# PCB2.net
KiCad netlist of a schematic drawn in Altium Designer
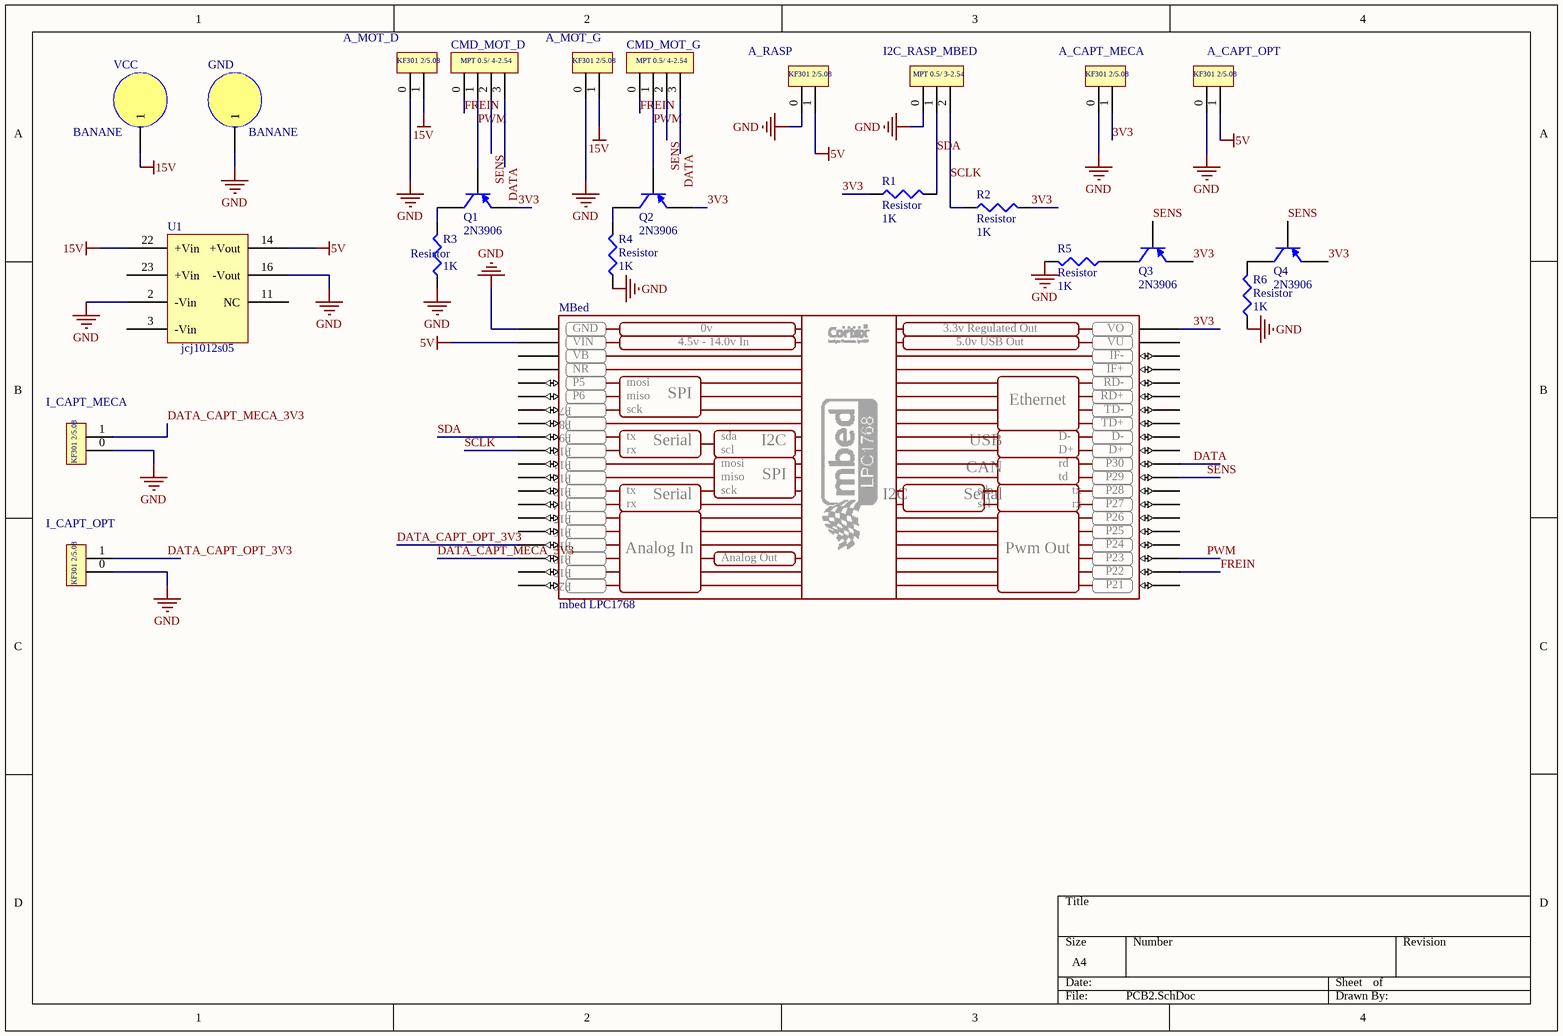
[diagram p0: PCB2.SchDoc]

(export (version "E")
  (design (tool "Eeschema 10.0.6"))
  (components
    (comp (ref "A_CAPT_MECA")
      (value "Screw Terminal 2/5.08")
      (footprint "KF301_2/5.08")
      (description "KF301 2 contacts / 5.08mm")
      (libsource (lib "Library_Polytech_Connector") (part "Screw Terminal 2/5.08"))
    )
    (comp (ref "A_CAPT_OPT")
      (value "Screw Terminal 2/5.08")
      (footprint "KF301_2/5.08")
      (description "KF301 2 contacts / 5.08mm")
      (libsource (lib "Library_Polytech_Connector") (part "Screw Terminal 2/5.08"))
    )
    (comp (ref "A_MOT_D")
      (value "Screw Terminal 2/5.08")
      (footprint "KF301_2/5.08")
      (description "KF301 2 contacts / 5.08mm")
      (libsource (lib "Library_Polytech_Connector") (part "Screw Terminal 2/5.08"))
    )
    (comp (ref "A_MOT_G")
      (value "Screw Terminal 2/5.08")
      (footprint "KF301_2/5.08")
      (description "KF301 2 contacts / 5.08mm")
      (libsource (lib "Library_Polytech_Connector") (part "Screw Terminal 2/5.08"))
    )
    (comp (ref "A_RASP")
      (value "Screw Terminal 2/5.08")
      (footprint "KF301_2/5.08")
      (description "KF301 2 contacts / 5.08mm")
      (libsource (lib "Library_Polytech_Connector") (part "Screw Terminal 2/5.08"))
    )
    (comp (ref "CMD_MOT_D")
      (value "Screw Terminal 4/2.54")
      (footprint "MPT_0.5-4-2.54")
      (description "MPT 0.5/ 4 contacts / 2.54mm")
      (libsource (lib "Library_Polytech_Connector") (part "Screw Terminal 4/2.54"))
    )
    (comp (ref "CMD_MOT_G")
      (value "Screw Terminal 4/2.54")
      (footprint "MPT_0.5-4-2.54")
      (description "MPT 0.5/ 4 contacts / 2.54mm")
      (libsource (lib "Library_Polytech_Connector") (part "Screw Terminal 4/2.54"))
    )
    (comp (ref "GND")
      (value "BANANE")
      (footprint "connecteur_banane_v0.1")
      (description "socket 4 mm with nut")
      (libsource (lib "Library_Polytech_Connector") (part "Socket 4 mm"))
    )
    (comp (ref "I2C_RASP_MBED")
      (value "Screw Terminal 3/2.54")
      (footprint "MPT_0.5-3-2.54")
      (description "MPT 0.5/ 3 contacts / 2.54mm")
      (libsource (lib "Library_Polytech_Connector") (part "Screw Terminal 3/2.54"))
    )
    (comp (ref "I_CAPT_MECA")
      (value "Screw Terminal 2/5.08")
      (footprint "KF301_2/5.08")
      (description "KF301 2 contacts / 5.08mm")
      (libsource (lib "") (part "Screw Terminal 2/5.08_1"))
    )
    (comp (ref "I_CAPT_OPT")
      (value "Screw Terminal 2/5.08")
      (footprint "KF301_2/5.08")
      (description "KF301 2 contacts / 5.08mm")
      (libsource (lib "") (part "Screw Terminal 2/5.08_1"))
    )
    (comp (ref "MBed")
      (value "mbed LPC1768")
      (footprint "DIP40-LARGE")
      (description "Prototyping Board")
      (libsource (lib "Library_Polytech_Actif") (part "mbed LPC1768"))
    )
    (comp (ref "Q1")
      (value "2N3906")
      (footprint "TO-92A")
      (description "PNP General Purpose Amplifier")
      (fields (field (name "PUBLISHER") "Altium Limited"))
      (libsource (lib "Miscellaneous Devices") (part "2N3906"))
    )
    (comp (ref "Q2")
      (value "2N3906")
      (footprint "TO-92A")
      (description "PNP General Purpose Amplifier")
      (fields (field (name "PUBLISHER") "Altium Limited"))
      (libsource (lib "Miscellaneous Devices") (part "2N3906"))
    )
    (comp (ref "Q3")
      (value "2N3906")
      (footprint "TO-92A")
      (description "PNP General Purpose Amplifier")
      (fields (field (name "PUBLISHER") "Altium Limited"))
      (libsource (lib "Miscellaneous Devices") (part "2N3906"))
    )
    (comp (ref "Q4")
      (value "2N3906")
      (footprint "TO-92A")
      (description "PNP General Purpose Amplifier")
      (fields (field (name "PUBLISHER") "Altium Limited"))
      (libsource (lib "Miscellaneous Devices") (part "2N3906"))
    )
    (comp (ref "R1")
      (value "Resistor")
      (footprint "AXIAL-0.6")
      (fields (field (name "ALTIUM_VALUE") "1K") (field (name "PUBLISHER") "Altium Limited"))
      (libsource (lib "Library_Polytech_Passif") (part "Resistor"))
    )
    (comp (ref "R2")
      (value "Resistor")
      (footprint "AXIAL-0.6")
      (fields (field (name "ALTIUM_VALUE") "1K") (field (name "PUBLISHER") "Altium Limited"))
      (libsource (lib "Library_Polytech_Passif") (part "Resistor"))
    )
    (comp (ref "R3")
      (value "Resistor")
      (footprint "AXIAL-0.6")
      (fields (field (name "ALTIUM_VALUE") "1K") (field (name "PUBLISHER") "Altium Limited"))
      (libsource (lib "Library_Polytech_Passif") (part "Resistor"))
    )
    (comp (ref "R4")
      (value "Resistor")
      (footprint "AXIAL-0.6")
      (fields (field (name "ALTIUM_VALUE") "1K") (field (name "PUBLISHER") "Altium Limited"))
      (libsource (lib "Library_Polytech_Passif") (part "Resistor"))
    )
    (comp (ref "R5")
      (value "Resistor")
      (footprint "AXIAL-0.6")
      (fields (field (name "ALTIUM_VALUE") "1K") (field (name "PUBLISHER") "Altium Limited"))
      (libsource (lib "Library_Polytech_Passif") (part "Resistor"))
    )
    (comp (ref "R6")
      (value "Resistor")
      (footprint "AXIAL-0.6")
      (fields (field (name "ALTIUM_VALUE") "1K") (field (name "PUBLISHER") "Altium Limited"))
      (libsource (lib "Library_Polytech_Passif") (part "Resistor"))
    )
    (comp (ref "U1")
      (value "jcj1012s05")
      (footprint "jcj1012s05")
      (libsource (lib "traveling") (part "jcj1012s05"))
    )
    (comp (ref "VCC")
      (value "BANANE")
      (footprint "connecteur_banane_v0.1")
      (description "socket 4 mm with nut")
      (libsource (lib "Library_Polytech_Connector") (part "Socket 4 mm"))
    )
  )
  (nets
    (net (code "1") (name "/3V3") (class "Default")
      (node (ref "A_CAPT_MECA") (pin "1") (pinfunction "1_1") (pintype "passive"))
      (node (ref "MBed") (pin "40") (pinfunction "VO_40") (pintype "power_in"))
      (node (ref "Q1") (pin "1") (pinfunction "E_1") (pintype "passive"))
      (node (ref "Q2") (pin "1") (pinfunction "E_1") (pintype "passive"))
      (node (ref "Q3") (pin "1") (pinfunction "E_1") (pintype "passive"))
      (node (ref "Q4") (pin "1") (pinfunction "E_1") (pintype "passive"))
      (node (ref "R1") (pin "1") (pinfunction "1_1") (pintype "passive"))
      (node (ref "R2") (pin "2") (pinfunction "2_2") (pintype "passive"))
    )
    (net (code "2") (name "/DATA") (class "Default")
      (node (ref "CMD_MOT_D") (pin "3") (pinfunction "3_3") (pintype "passive"))
      (node (ref "CMD_MOT_G") (pin "3") (pinfunction "3_3") (pintype "passive"))
      (node (ref "MBed") (pin "30") (pinfunction "P30_30") (pintype "bidirectional"))
    )
    (net (code "3") (name "/DATA_CAPT_MECA_3V3") (class "Default")
      (node (ref "I_CAPT_MECA") (pin "1") (pinfunction "1_1") (pintype "passive"))
      (node (ref "MBed") (pin "18") (pinfunction "P18_18") (pintype "bidirectional"))
    )
    (net (code "4") (name "/DATA_CAPT_OPT_3V3") (class "Default")
      (node (ref "I_CAPT_OPT") (pin "1") (pinfunction "1_1") (pintype "passive"))
      (node (ref "MBed") (pin "17") (pinfunction "P17_17") (pintype "bidirectional"))
    )
    (net (code "5") (name "/FREIN") (class "Default")
      (node (ref "CMD_MOT_D") (pin "0") (pinfunction "0_0") (pintype "passive"))
      (node (ref "CMD_MOT_G") (pin "0") (pinfunction "0_0") (pintype "passive"))
      (node (ref "MBed") (pin "22") (pinfunction "P22_22") (pintype "bidirectional"))
    )
    (net (code "6") (name "/PWM") (class "Default")
      (node (ref "CMD_MOT_D") (pin "1") (pinfunction "1_1") (pintype "passive"))
      (node (ref "CMD_MOT_G") (pin "1") (pinfunction "1_1") (pintype "passive"))
      (node (ref "MBed") (pin "23") (pinfunction "P23_23") (pintype "bidirectional"))
      (node (ref "Q1") (pin "2") (pinfunction "B_2") (pintype "passive"))
      (node (ref "Q2") (pin "2") (pinfunction "B_2") (pintype "passive"))
    )
    (net (code "7") (name "/SCLK") (class "Default")
      (node (ref "I2C_RASP_MBED") (pin "2") (pinfunction "2_2") (pintype "passive"))
      (node (ref "MBed") (pin "10") (pinfunction "P10_10") (pintype "bidirectional"))
      (node (ref "R2") (pin "1") (pinfunction "1_1") (pintype "passive"))
    )
    (net (code "8") (name "/SDA") (class "Default")
      (node (ref "I2C_RASP_MBED") (pin "1") (pinfunction "1_1") (pintype "passive"))
      (node (ref "MBed") (pin "9") (pinfunction "P9_9") (pintype "bidirectional"))
      (node (ref "R1") (pin "2") (pinfunction "2_2") (pintype "passive"))
    )
    (net (code "9") (name "/SENS") (class "Default")
      (node (ref "CMD_MOT_D") (pin "2") (pinfunction "2_2") (pintype "passive"))
      (node (ref "CMD_MOT_G") (pin "2") (pinfunction "2_2") (pintype "passive"))
      (node (ref "MBed") (pin "29") (pinfunction "P29_29") (pintype "bidirectional"))
      (node (ref "Q3") (pin "2") (pinfunction "B_2") (pintype "passive"))
      (node (ref "Q4") (pin "2") (pinfunction "B_2") (pintype "passive"))
    )
    (net (code "10") (name "5V") (class "Default")
      (node (ref "A_CAPT_OPT") (pin "1") (pinfunction "1_1") (pintype "passive"))
      (node (ref "A_RASP") (pin "1") (pinfunction "1_1") (pintype "passive"))
      (node (ref "MBed") (pin "2") (pinfunction "VIN_2") (pintype "power_in"))
      (node (ref "U1") (pin "14") (pinfunction "+Vout_14") (pintype "passive"))
    )
    (net (code "11") (name "15V") (class "Default")
      (node (ref "A_MOT_D") (pin "1") (pinfunction "1_1") (pintype "passive"))
      (node (ref "A_MOT_G") (pin "1") (pinfunction "1_1") (pintype "passive"))
      (node (ref "U1") (pin "22") (pinfunction "+Vin_22") (pintype "passive"))
      (node (ref "VCC") (pin "1") (pinfunction "1_1") (pintype "passive"))
    )
    (net (code "12") (name "GND") (class "Default")
      (node (ref "A_CAPT_MECA") (pin "0") (pinfunction "0_0") (pintype "passive"))
      (node (ref "A_CAPT_OPT") (pin "0") (pinfunction "0_0") (pintype "passive"))
      (node (ref "A_MOT_D") (pin "0") (pinfunction "0_0") (pintype "passive"))
      (node (ref "A_MOT_G") (pin "0") (pinfunction "0_0") (pintype "passive"))
      (node (ref "A_RASP") (pin "0") (pinfunction "0_0") (pintype "passive"))
      (node (ref "GND") (pin "1") (pinfunction "1_1") (pintype "passive"))
      (node (ref "I2C_RASP_MBED") (pin "0") (pinfunction "0_0") (pintype "passive"))
      (node (ref "I_CAPT_MECA") (pin "0") (pinfunction "0_0") (pintype "passive"))
      (node (ref "I_CAPT_OPT") (pin "0") (pinfunction "0_0") (pintype "passive"))
      (node (ref "MBed") (pin "1") (pinfunction "GND_1") (pintype "power_in"))
      (node (ref "R3") (pin "1") (pinfunction "1_1") (pintype "passive"))
      (node (ref "R4") (pin "1") (pinfunction "1_1") (pintype "passive"))
      (node (ref "R5") (pin "2") (pinfunction "2_2") (pintype "passive"))
      (node (ref "R6") (pin "1") (pinfunction "1_1") (pintype "passive"))
      (node (ref "U1") (pin "16") (pinfunction "-Vout_16") (pintype "passive"))
      (node (ref "U1") (pin "2") (pinfunction "-Vin_2") (pintype "passive"))
    )
    (net (code "13") (name "Net-(Q1-C)") (class "Default")
      (node (ref "Q1") (pin "3") (pinfunction "C_3") (pintype "passive"))
      (node (ref "R3") (pin "2") (pinfunction "2_2") (pintype "passive"))
    )
    (net (code "14") (name "Net-(Q2-C)") (class "Default")
      (node (ref "Q2") (pin "3") (pinfunction "C_3") (pintype "passive"))
      (node (ref "R4") (pin "2") (pinfunction "2_2") (pintype "passive"))
    )
    (net (code "15") (name "Net-(Q3-C)") (class "Default")
      (node (ref "Q3") (pin "3") (pinfunction "C_3") (pintype "passive"))
      (node (ref "R5") (pin "1") (pinfunction "1_1") (pintype "passive"))
    )
    (net (code "16") (name "Net-(Q4-C)") (class "Default")
      (node (ref "Q4") (pin "3") (pinfunction "C_3") (pintype "passive"))
      (node (ref "R6") (pin "2") (pinfunction "2_2") (pintype "passive"))
    )
    (net (code "17") (name "unconnected-(MBed-D+-Pad31)") (class "Default")
      (node (ref "MBed") (pin "31") (pinfunction "D+_31") (pintype "bidirectional"))
    )
    (net (code "18") (name "unconnected-(MBed-D--Pad32)") (class "Default")
      (node (ref "MBed") (pin "32") (pinfunction "D-_32") (pintype "bidirectional"))
    )
    (net (code "19") (name "unconnected-(MBed-IF+-Pad37)") (class "Default")
      (node (ref "MBed") (pin "37") (pinfunction "IF+_37") (pintype "bidirectional"))
    )
    (net (code "20") (name "unconnected-(MBed-IF--Pad38)") (class "Default")
      (node (ref "MBed") (pin "38") (pinfunction "IF-_38") (pintype "bidirectional"))
    )
    (net (code "21") (name "unconnected-(MBed-NR-Pad4)") (class "Default")
      (node (ref "MBed") (pin "4") (pinfunction "NR_4") (pintype "power_in"))
    )
    (net (code "22") (name "unconnected-(MBed-P5-Pad5)") (class "Default")
      (node (ref "MBed") (pin "5") (pinfunction "P5_5") (pintype "bidirectional"))
    )
    (net (code "23") (name "unconnected-(MBed-P6-Pad6)") (class "Default")
      (node (ref "MBed") (pin "6") (pinfunction "P6_6") (pintype "bidirectional"))
    )
    (net (code "24") (name "unconnected-(MBed-P7-Pad7)") (class "Default")
      (node (ref "MBed") (pin "7") (pinfunction "P7_7") (pintype "bidirectional"))
    )
    (net (code "25") (name "unconnected-(MBed-P8-Pad8)") (class "Default")
      (node (ref "MBed") (pin "8") (pinfunction "P8_8") (pintype "bidirectional"))
    )
    (net (code "26") (name "unconnected-(MBed-P11-Pad11)") (class "Default")
      (node (ref "MBed") (pin "11") (pinfunction "P11_11") (pintype "bidirectional"))
    )
    (net (code "27") (name "unconnected-(MBed-P12-Pad12)") (class "Default")
      (node (ref "MBed") (pin "12") (pinfunction "P12_12") (pintype "bidirectional"))
    )
    (net (code "28") (name "unconnected-(MBed-P13-Pad13)") (class "Default")
      (node (ref "MBed") (pin "13") (pinfunction "P13_13") (pintype "bidirectional"))
    )
    (net (code "29") (name "unconnected-(MBed-P14-Pad14)") (class "Default")
      (node (ref "MBed") (pin "14") (pinfunction "P14_14") (pintype "bidirectional"))
    )
    (net (code "30") (name "unconnected-(MBed-P15-Pad15)") (class "Default")
      (node (ref "MBed") (pin "15") (pinfunction "P15_15") (pintype "bidirectional"))
    )
    (net (code "31") (name "unconnected-(MBed-P16-Pad16)") (class "Default")
      (node (ref "MBed") (pin "16") (pinfunction "P16_16") (pintype "bidirectional"))
    )
    (net (code "32") (name "unconnected-(MBed-P19-Pad19)") (class "Default")
      (node (ref "MBed") (pin "19") (pinfunction "P19_19") (pintype "bidirectional"))
    )
    (net (code "33") (name "unconnected-(MBed-P20-Pad20)") (class "Default")
      (node (ref "MBed") (pin "20") (pinfunction "P20_20") (pintype "bidirectional"))
    )
    (net (code "34") (name "unconnected-(MBed-P21-Pad21)") (class "Default")
      (node (ref "MBed") (pin "21") (pinfunction "P21_21") (pintype "bidirectional"))
    )
    (net (code "35") (name "unconnected-(MBed-P24-Pad24)") (class "Default")
      (node (ref "MBed") (pin "24") (pinfunction "P24_24") (pintype "bidirectional"))
    )
    (net (code "36") (name "unconnected-(MBed-P25-Pad25)") (class "Default")
      (node (ref "MBed") (pin "25") (pinfunction "P25_25") (pintype "bidirectional"))
    )
    (net (code "37") (name "unconnected-(MBed-P26-Pad26)") (class "Default")
      (node (ref "MBed") (pin "26") (pinfunction "P26_26") (pintype "bidirectional"))
    )
    (net (code "38") (name "unconnected-(MBed-P27-Pad27)") (class "Default")
      (node (ref "MBed") (pin "27") (pinfunction "P27_27") (pintype "bidirectional"))
    )
    (net (code "39") (name "unconnected-(MBed-P28-Pad28)") (class "Default")
      (node (ref "MBed") (pin "28") (pinfunction "P28_28") (pintype "bidirectional"))
    )
    (net (code "40") (name "unconnected-(MBed-RD+-Pad35)") (class "Default")
      (node (ref "MBed") (pin "35") (pinfunction "RD+_35") (pintype "bidirectional"))
    )
    (net (code "41") (name "unconnected-(MBed-RD--Pad36)") (class "Default")
      (node (ref "MBed") (pin "36") (pinfunction "RD-_36") (pintype "bidirectional"))
    )
    (net (code "42") (name "unconnected-(MBed-TD+-Pad33)") (class "Default")
      (node (ref "MBed") (pin "33") (pinfunction "TD+_33") (pintype "bidirectional"))
    )
    (net (code "43") (name "unconnected-(MBed-TD--Pad34)") (class "Default")
      (node (ref "MBed") (pin "34") (pinfunction "TD-_34") (pintype "bidirectional"))
    )
    (net (code "44") (name "unconnected-(MBed-VB-Pad3)") (class "Default")
      (node (ref "MBed") (pin "3") (pinfunction "VB_3") (pintype "power_in"))
    )
    (net (code "45") (name "unconnected-(MBed-VU-Pad39)") (class "Default")
      (node (ref "MBed") (pin "39") (pinfunction "VU_39") (pintype "power_in"))
    )
    (net (code "46") (name "unconnected-(U1-+Vin-Pad23)") (class "Default")
      (node (ref "U1") (pin "23") (pinfunction "+Vin_23") (pintype "passive"))
    )
    (net (code "47") (name "unconnected-(U1--Vin-Pad3)") (class "Default")
      (node (ref "U1") (pin "3") (pinfunction "-Vin_3") (pintype "passive"))
    )
    (net (code "48") (name "unconnected-(U1-NC-Pad11)") (class "Default")
      (node (ref "U1") (pin "11") (pinfunction "NC_11") (pintype "passive"))
    )
  )
)
